# skematik_relay.net
KiCad netlist of a schematic drawn in EAGLE
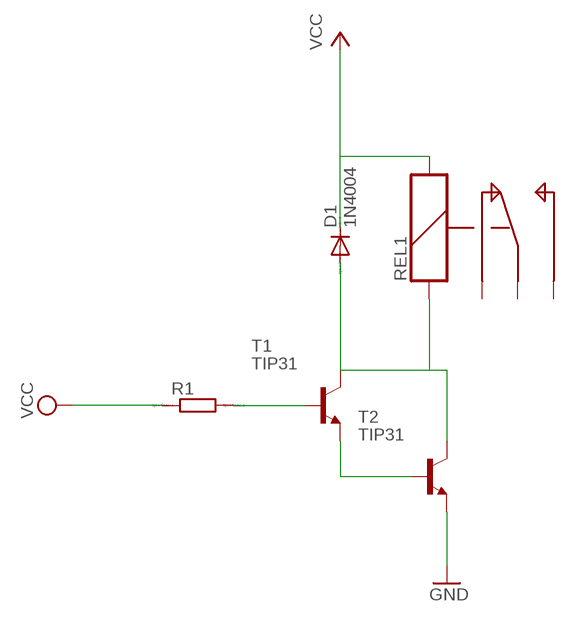
[diagram p0: schematic, sheet 1]

(export (version "E")
  (design (tool "Eeschema 10.0.6"))
  (components
    (comp (ref "D1")
      (value "1N4004")
      (footprint "eagle-import:DO41-10")
      (libsource (lib "eagle-import") (part "1N4004"))
    )
    (comp (ref "R1")
      (value "R-EU_0204_5")
      (footprint "eagle-import:0204_5")
      (libsource (lib "eagle-import") (part "R-EU_0204_5"))
    )
    (comp (ref "REL1")
      (value "REL-5PIN")
      (footprint "eagle-import:REL-5PIN")
      (libsource (lib "eagle-import") (part "REL-5PIN"))
    )
    (comp (ref "T1")
      (value "TIP31")
      (footprint "eagle-import:TO220")
      (libsource (lib "eagle-import") (part "TIP31"))
    )
    (comp (ref "T2")
      (value "TIP31")
      (footprint "eagle-import:TO220")
      (libsource (lib "eagle-import") (part "TIP31"))
    )
  )
  (nets
    (net (code "1") (name "GND") (class "Default")
      (node (ref "T2") (pin "3") (pinfunction "E_3") (pintype "passive"))
    )
    (net (code "2") (name "Net-(T1-B)") (class "Default")
      (node (ref "R1") (pin "2") (pinfunction "2_2") (pintype "passive"))
      (node (ref "T1") (pin "1") (pinfunction "B_1") (pintype "passive"))
    )
    (net (code "3") (name "Net-(T1-C)") (class "Default")
      (node (ref "D1") (pin "A") (pinfunction "A_A") (pintype "passive"))
      (node (ref "REL1") (pin "S1") (pinfunction "S1_S1") (pintype "passive"))
      (node (ref "T1") (pin "2") (pinfunction "C_2") (pintype "passive"))
      (node (ref "T2") (pin "2") (pinfunction "C_2") (pintype "passive"))
    )
    (net (code "4") (name "Net-(T1-E)") (class "Default")
      (node (ref "T1") (pin "3") (pinfunction "E_3") (pintype "passive"))
      (node (ref "T2") (pin "1") (pinfunction "B_1") (pintype "passive"))
    )
    (net (code "5") (name "VCC") (class "Default")
      (node (ref "D1") (pin "C") (pinfunction "C_C") (pintype "passive"))
      (node (ref "R1") (pin "1") (pinfunction "1_1") (pintype "passive"))
      (node (ref "REL1") (pin "S2") (pinfunction "S2_S2") (pintype "passive"))
    )
    (net (code "6") (name "unconnected-(REL1-PadC)") (class "Default")
      (node (ref "REL1") (pin "C") (pinfunction "C_C") (pintype "passive"))
    )
    (net (code "7") (name "unconnected-(REL1-PadO)") (class "Default")
      (node (ref "REL1") (pin "O") (pinfunction "O_O") (pintype "passive"))
    )
    (net (code "8") (name "unconnected-(REL1-PadS)") (class "Default")
      (node (ref "REL1") (pin "S") (pinfunction "S_S") (pintype "passive"))
    )
  )
)
